# bg_MCU.net
KiCad netlist of a schematic drawn in Altium Designer
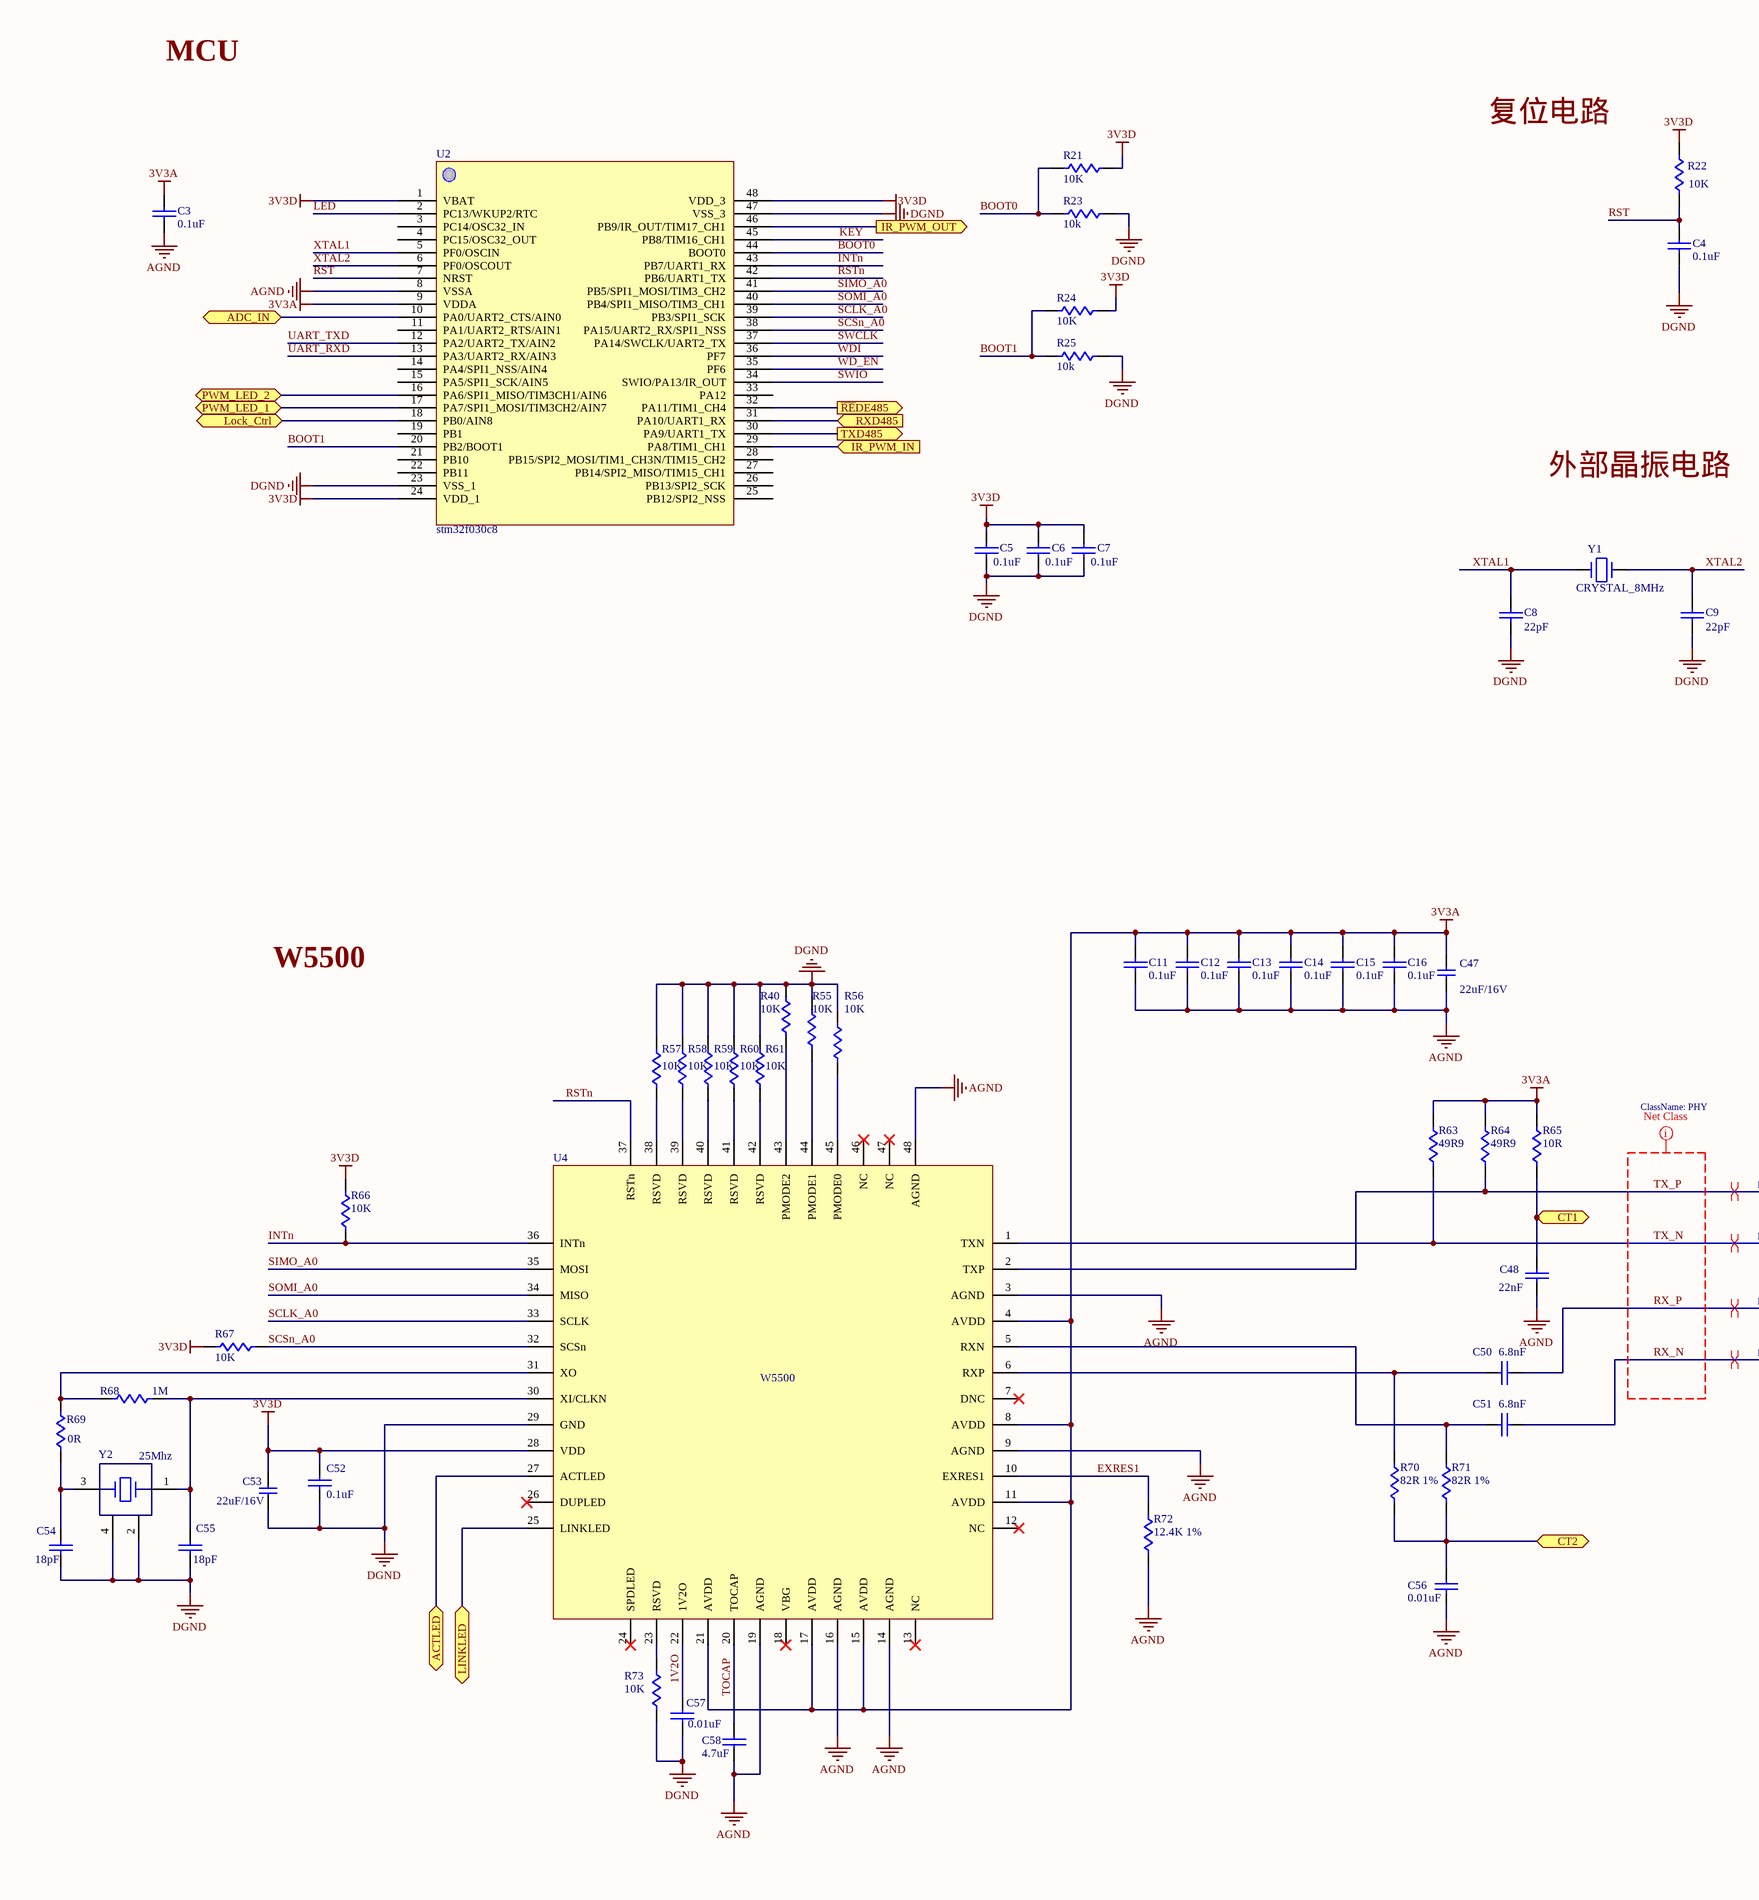
[diagram p0: bg_MCU.SchDoc, left]
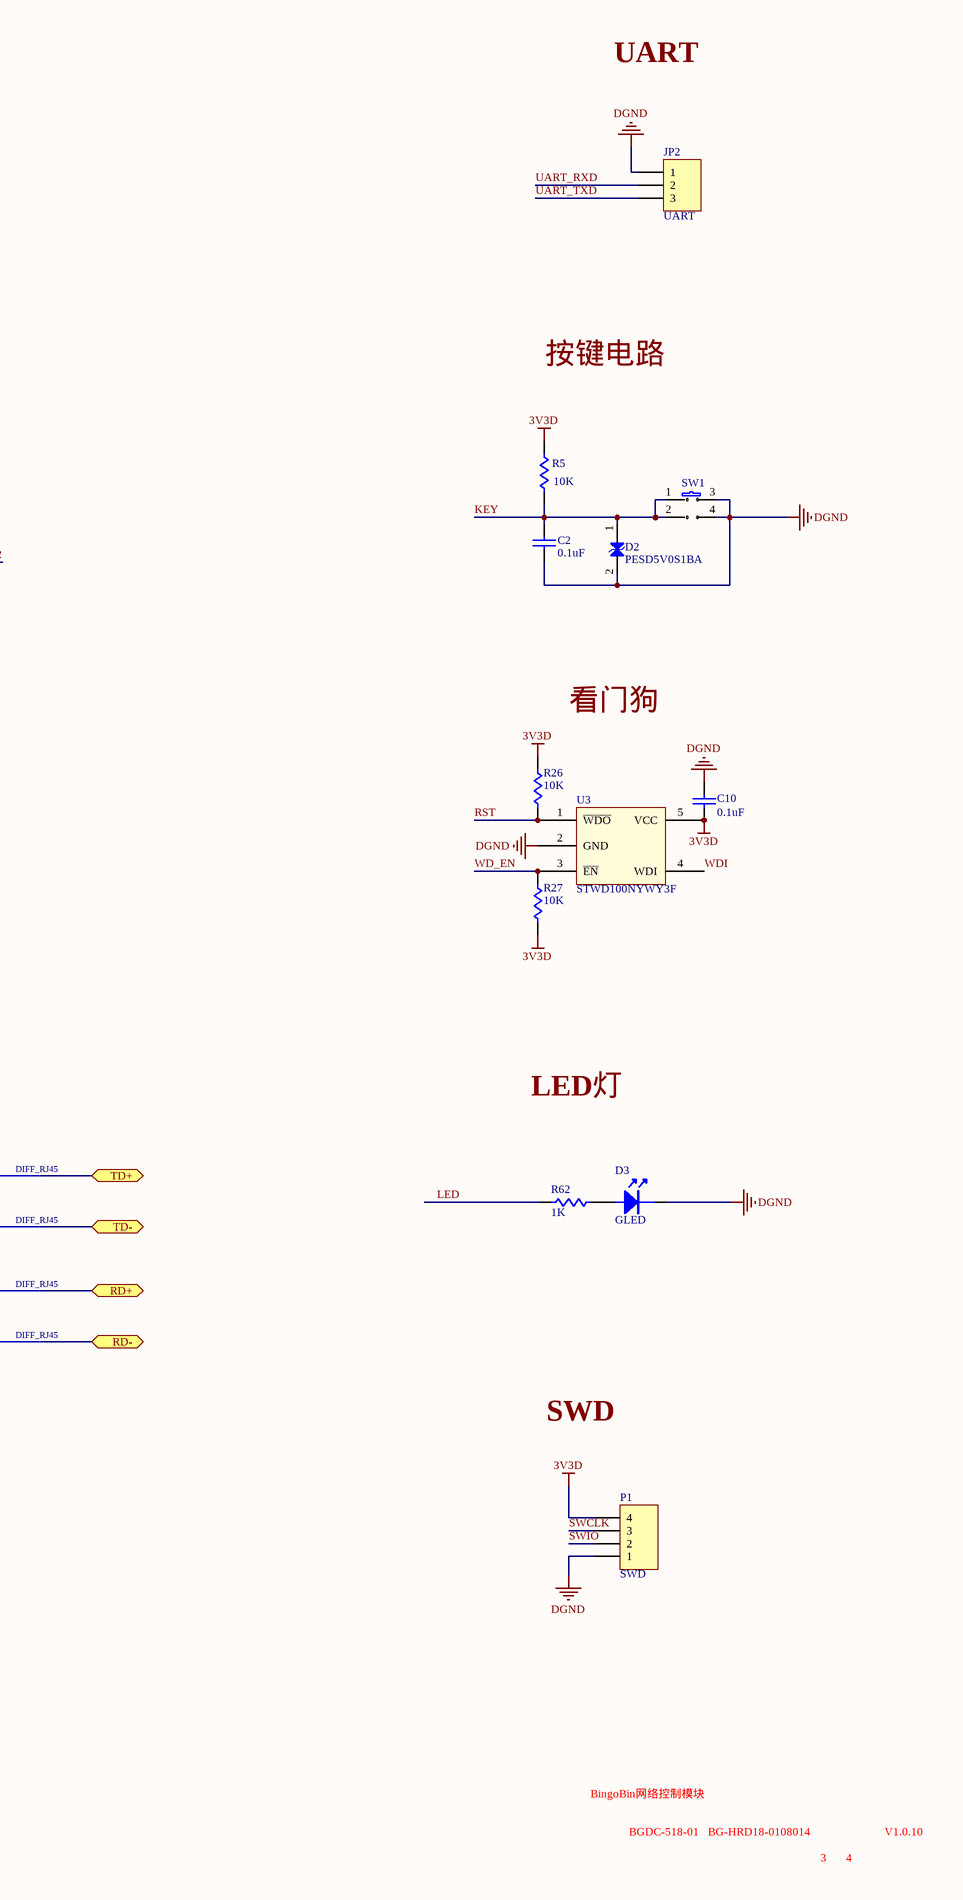
[diagram p1: bg_MCU.SchDoc, right]

(export (version "E")
  (design (tool "Eeschema 10.0.6"))
  (components
    (comp (ref "C2")
      (value "0.1uF")
      (footprint "C0603")
      (description "Capacitor, Ceramic, 0.1uF, 16V, 10%, 0603, X7R")
      (libsource (lib "bg_sch") (part "C0603"))
    )
    (comp (ref "C3")
      (value "0.1uF")
      (footprint "C0603")
      (description "Capacitor, Ceramic, 0.1uF, 16V, 10%, 0603, X7R")
      (libsource (lib "bg_sch") (part "C0603"))
    )
    (comp (ref "C4")
      (value "0.1uF")
      (footprint "C0603")
      (description "Capacitor, Ceramic, 0.1uF, 16V, 10%, 0603, X7R")
      (libsource (lib "bg_sch") (part "C0603"))
    )
    (comp (ref "C5")
      (value "0.1uF")
      (footprint "C0603")
      (description "Capacitor, Ceramic, 0.1uF, 16V, 10%, 0603, X7R")
      (libsource (lib "bg_sch") (part "C0603"))
    )
    (comp (ref "C6")
      (value "0.1uF")
      (footprint "C0603")
      (description "Capacitor, Ceramic, 0.1uF, 16V, 10%, 0603, X7R")
      (libsource (lib "bg_sch") (part "C0603"))
    )
    (comp (ref "C7")
      (value "0.1uF")
      (footprint "C0603")
      (description "Capacitor, Ceramic, 0.1uF, 16V, 10%, 0603, X7R")
      (libsource (lib "bg_sch") (part "C0603"))
    )
    (comp (ref "C8")
      (value "22pF")
      (footprint "C0603")
      (description "Capacitor, Ceramic, 22pF, 50V, 5%, 0603, COG")
      (libsource (lib "bg_sch") (part "C0603"))
    )
    (comp (ref "C9")
      (value "22pF")
      (footprint "C0603")
      (description "Capacitor, Ceramic, 22pF, 50V, 5%, 0603, COG")
      (libsource (lib "bg_sch") (part "C0603"))
    )
    (comp (ref "C10")
      (value "0.1uF")
      (footprint "C0603")
      (description "Capacitor, Ceramic, 0.1uF, 16V, 10%, 0603, X7R")
      (libsource (lib "bg_sch") (part "C0603"))
    )
    (comp (ref "C11")
      (value "0.1uF")
      (footprint "C0603")
      (description "Capacitor, Ceramic, 0.1uF, 16V, 10%, 0603, X7R")
      (libsource (lib "bg_sch") (part "C0603"))
    )
    (comp (ref "C12")
      (value "0.1uF")
      (footprint "C0603")
      (description "Capacitor, Ceramic, 0.1uF, 16V, 10%, 0603, X7R")
      (libsource (lib "bg_sch") (part "C0603"))
    )
    (comp (ref "C13")
      (value "0.1uF")
      (footprint "C0603")
      (description "Capacitor, Ceramic, 0.1uF, 16V, 10%, 0603, X7R")
      (libsource (lib "bg_sch") (part "C0603"))
    )
    (comp (ref "C14")
      (value "0.1uF")
      (footprint "C0603")
      (description "Capacitor, Ceramic, 0.1uF, 16V, 10%, 0603, X7R")
      (libsource (lib "bg_sch") (part "C0603"))
    )
    (comp (ref "C15")
      (value "0.1uF")
      (footprint "C0603")
      (description "Capacitor, Ceramic, 0.1uF, 16V, 10%, 0603, X7R")
      (libsource (lib "bg_sch") (part "C0603"))
    )
    (comp (ref "C16")
      (value "0.1uF")
      (footprint "C0603")
      (description "Capacitor, Ceramic, 0.1uF, 16V, 10%, 0603, X7R")
      (libsource (lib "bg_sch") (part "C0603"))
    )
    (comp (ref "C47")
      (value "22uF/16V")
      (footprint "C1210")
      (description "Capacitor, Ceramic, 10uF,16V, 10%,1210,X5R")
      (fields (field (name "PART NUMBER") "C0603-4µ7") (field (name "PUBLISHER") "Nordic Semiconductor"))
      (libsource (lib "sistalk") (part "CAP_0603"))
    )
    (comp (ref "C48")
      (value "22nF")
      (footprint "C0603")
      (description "Capacitor, Ceramic, 22nF, 25V, 10%, 0603, X7R")
      (libsource (lib "bg_sch") (part "C0603"))
    )
    (comp (ref "C50")
      (value "6.8nF")
      (footprint "C0603")
      (description "Capacitor, Ceramic, 6.8nF, 50V, 10%, 0603, X7R")
      (libsource (lib "bg_sch") (part "C0603"))
    )
    (comp (ref "C51")
      (value "6.8nF")
      (footprint "C0603")
      (description "Capacitor, Ceramic, 6.8nF, 50V, 10%, 0603, X7R")
      (libsource (lib "bg_sch") (part "C0603"))
    )
    (comp (ref "C52")
      (value "0.1uF")
      (footprint "C0603")
      (description "Capacitor, Ceramic, 0.1uF, 16V, 10%, 0603, X7R")
      (libsource (lib "bg_sch") (part "C0603"))
    )
    (comp (ref "C53")
      (value "22uF/16V")
      (footprint "C1210")
      (description "Capacitor, Ceramic, 10uF,16V, 10%,1210,X5R")
      (fields (field (name "PART NUMBER") "C0603-4µ7") (field (name "PUBLISHER") "Nordic Semiconductor"))
      (libsource (lib "sistalk") (part "CAP_0603"))
    )
    (comp (ref "C54")
      (value "18pF")
      (footprint "C0603")
      (description "Capacitor, Ceramic, 18pF, 50V, 5%, 0603, COG")
      (libsource (lib "bg_sch") (part "C0603"))
    )
    (comp (ref "C55")
      (value "18pF")
      (footprint "C0603")
      (description "Capacitor, Ceramic, 18pF, 50V, 5%, 0603, COG")
      (libsource (lib "bg_sch") (part "C0603"))
    )
    (comp (ref "C56")
      (value "0.01uF")
      (footprint "C0603")
      (description "Capacitor, Ceramic, 0.01uF, 50V, 10%, 0603, X7R")
      (libsource (lib "bg_sch") (part "C0603"))
    )
    (comp (ref "C57")
      (value "0.01uF")
      (footprint "C0603")
      (description "Capacitor, Ceramic, 0.01uF, 50V, 10%, 0603, X7R")
      (libsource (lib "bg_sch") (part "C0603"))
    )
    (comp (ref "C58")
      (value "4.7uF")
      (footprint "C0603")
      (description "Capacitor, Ceramic, 4.7uF, 16V, 10%, 0603, X7R")
      (libsource (lib "bg_sch") (part "C0603"))
    )
    (comp (ref "D2")
      (value "PESD5V0S1BA")
      (footprint "SOD323")
      (fields (field (name "MANUFACTURER") "NXP"))
      (libsource (lib "bingo") (part "ESD"))
    )
    (comp (ref "D3")
      (value "GLED")
      (footprint "LED-0805")
      (description "翠绿色 贴片LED ( Iv=220-270mcd @IF=5mA) ")
      (libsource (lib "bg_sch") (part "LED_0805"))
    )
    (comp (ref "JP2")
      (value "UART")
      (footprint "HDR1X3")
      (description "Header, 3-Pin, Single row")
      (fields (field (name "PUBLISHER") "Altium Limited"))
      (libsource (lib "Miscellaneous Connectors") (part "Header 3"))
    )
    (comp (ref "P1")
      (value "SWD")
      (footprint "HDR1X4")
      (description "Header, 4-Pin")
      (fields (field (name "PUBLISHER") "Altium Limited"))
      (libsource (lib "Miscellaneous Connectors") (part "Header 4"))
    )
    (comp (ref "R5")
      (value "10K")
      (footprint "R0603")
      (description "RES, THICK FILM, 4.7K, 5%, 1/10W, 0603")
      (libsource (lib "bg_sch") (part "R0603"))
    )
    (comp (ref "R21")
      (value "10K")
      (footprint "R0603")
      (description "RES, THICK FILM, 4.7K, 5%, 1/10W, 0603")
      (libsource (lib "bg_sch") (part "R0603"))
    )
    (comp (ref "R22")
      (value "10K")
      (footprint "R0603")
      (description "RES, THICK FILM, 4.7K, 5%, 1/10W, 0603")
      (libsource (lib "bg_sch") (part "R0603"))
    )
    (comp (ref "R23")
      (value "10k")
      (footprint "R0603")
      (description "RES, THICK FILM, 4.7K, 5%, 1/10W, 0603")
      (libsource (lib "bg_sch") (part "R0603"))
    )
    (comp (ref "R24")
      (value "10K")
      (footprint "R0603")
      (description "RES, THICK FILM, 4.7K, 5%, 1/10W, 0603")
      (libsource (lib "bg_sch") (part "R0603"))
    )
    (comp (ref "R25")
      (value "10k")
      (footprint "R0603")
      (description "RES, THICK FILM, 4.7K, 5%, 1/10W, 0603")
      (libsource (lib "bg_sch") (part "R0603"))
    )
    (comp (ref "R26")
      (value "10K")
      (footprint "R0603")
      (description "RES, THICK FILM, 10K, 5%, 1/10W, 0603")
      (libsource (lib "bg_sch") (part "R0603"))
    )
    (comp (ref "R27")
      (value "10K")
      (footprint "R0603")
      (description "RES, THICK FILM, 10K, 5%, 1/10W, 0603")
      (libsource (lib "bg_sch") (part "R0603"))
    )
    (comp (ref "R40")
      (value "10K")
      (footprint "R0603")
      (description "RES, THICK FILM, 10K, 5%, 1/10W, 0603")
      (libsource (lib "bg_sch") (part "R0603"))
    )
    (comp (ref "R55")
      (value "10K")
      (footprint "R0603")
      (description "RES, THICK FILM, 10K, 5%, 1/10W, 0603")
      (libsource (lib "bg_sch") (part "R0603"))
    )
    (comp (ref "R56")
      (value "10K")
      (footprint "R0603")
      (description "RES, THICK FILM, 10K, 5%, 1/10W, 0603")
      (libsource (lib "bg_sch") (part "R0603"))
    )
    (comp (ref "R57")
      (value "10K")
      (footprint "R0603")
      (description "RES, THICK FILM, 10K, 5%, 1/10W, 0603")
      (libsource (lib "bg_sch") (part "R0603"))
    )
    (comp (ref "R58")
      (value "10K")
      (footprint "R0603")
      (description "RES, THICK FILM, 10K, 5%, 1/10W, 0603")
      (libsource (lib "bg_sch") (part "R0603"))
    )
    (comp (ref "R59")
      (value "10K")
      (footprint "R0603")
      (description "RES, THICK FILM, 10K, 5%, 1/10W, 0603")
      (libsource (lib "bg_sch") (part "R0603"))
    )
    (comp (ref "R60")
      (value "10K")
      (footprint "R0603")
      (description "RES, THICK FILM, 10K, 5%, 1/10W, 0603")
      (libsource (lib "bg_sch") (part "R0603"))
    )
    (comp (ref "R61")
      (value "10K")
      (footprint "R0603")
      (description "RES, THICK FILM, 10K, 5%, 1/10W, 0603")
      (libsource (lib "bg_sch") (part "R0603"))
    )
    (comp (ref "R62")
      (value "1K")
      (footprint "R0603")
      (description "RES, THICK FILM, 1K, 5%, 1/10W, 0603")
      (libsource (lib "bg_sch") (part "R0603"))
    )
    (comp (ref "R63")
      (value "49R9")
      (footprint "R0603")
      (description "RES, THICK FILM, 49.9 OHM, 1%, 1/10W, 0603")
      (libsource (lib "bg_sch") (part "R0603"))
    )
    (comp (ref "R64")
      (value "49R9")
      (footprint "R0603")
      (description "RES, THICK FILM, 49.9 OHM, 1%, 1/10W, 0603")
      (libsource (lib "bg_sch") (part "R0603"))
    )
    (comp (ref "R65")
      (value "10R")
      (footprint "R0603")
      (description "RES, THICK FILM, 10 OHM, 5%, 1/10W, 0603")
      (libsource (lib "bg_sch") (part "R0603"))
    )
    (comp (ref "R66")
      (value "10K")
      (footprint "R0603")
      (description "RES, THICK FILM, 10K, 5%, 1/10W, 0603")
      (libsource (lib "bg_sch") (part "R0603"))
    )
    (comp (ref "R67")
      (value "10K")
      (footprint "R0603")
      (description "RES, THICK FILM, 10K, 5%, 1/10W, 0603")
      (libsource (lib "bg_sch") (part "R0603"))
    )
    (comp (ref "R68")
      (value "1M")
      (footprint "R0603")
      (description "RES, THICK FILM, 1M, 5%, 1/10W, 0603")
      (libsource (lib "bg_sch") (part "R0603"))
    )
    (comp (ref "R69")
      (value "0R")
      (footprint "R0603")
      (description "RES, THICK FILM, 0 OHM, 1%, 1/10W, 0603")
      (libsource (lib "bg_sch") (part "R0603"))
    )
    (comp (ref "R70")
      (value "82R 1%")
      (footprint "R0603")
      (description "RES, THICK FILM, 82 OHM, 5%, 1/10W, 0603")
      (libsource (lib "bg_sch") (part "R0603"))
    )
    (comp (ref "R71")
      (value "82R 1%")
      (footprint "R0603")
      (description "RES, THICK FILM, 82 OHM, 5%, 1/10W, 0603")
      (libsource (lib "bg_sch") (part "R0603"))
    )
    (comp (ref "R72")
      (value "12.4K 1%")
      (footprint "R0603")
      (description "RES, THICK FILM, 12.4K, 1%, 1/10W, 0603")
      (libsource (lib "bg_sch") (part "R0603"))
    )
    (comp (ref "R73")
      (value "10K")
      (footprint "R0603")
      (description "RES, THICK FILM, 10K, 5%, 1/10W, 0603")
      (libsource (lib "bg_sch") (part "R0603"))
    )
    (comp (ref "SW1")
      (value "K2-6639SP-I4SC-04")
      (footprint "KEY6*6mm")
      (fields (field (name "MANUFACTURER") "韩国韩荣"))
      (libsource (lib "bingo") (part "SW"))
    )
    (comp (ref "U2")
      (value "stm32f030c8")
      (footprint "LQFP48")
      (description "mcu  LQFP-48_7x7x05P")
      (libsource (lib "bingo") (part "stm32f030c8"))
    )
    (comp (ref "U3")
      (value "STWD100NYWY3F")
      (footprint "SOT23-5")
      (description "Watchdog timer circuit/1.6s")
      (libsource (lib "bingo") (part "STWD100"))
    )
    (comp (ref "U4")
      (value "W5500")
      (footprint "W5500-LQFP-48_7x7x05P")
      (description "TCP/IP嵌入式以太网控制器")
      (libsource (lib "bg_sch") (part "W5500"))
    )
    (comp (ref "Y1")
      (value "CRYSTAL_8MHz")
      (footprint "8M_SMD_CRYSTAL")
      (description "20PF 20PPM -40~+85℃ 编带")
      (libsource (lib "bg_sch") (part "CRYSTAL_32.768k"))
    )
    (comp (ref "Y2")
      (value "25Mhz")
      (footprint "25MHz-SMD-3225_4P")
      (description "XTAL S3225 25M 12pF 10ppm 40R -20~70℃ ")
      (libsource (lib "bg_sch") (part "25Mhz"))
    )
  )
  (nets
    (net (code "1") (name "/1V2O") (class "Default")
      (node (ref "C57") (pin "1") (pinfunction "1_1") (pintype "passive"))
      (node (ref "U4") (pin "22") (pinfunction "1V2O_22") (pintype "passive"))
    )
    (net (code "2") (name "/ACTLED") (class "Default")
      (node (ref "U4") (pin "27") (pinfunction "ACTLED_27") (pintype "passive"))
    )
    (net (code "3") (name "/ADC_IN") (class "Default")
      (node (ref "U2") (pin "10") (pinfunction "PA0/UART2_CTS/AIN0_10") (pintype "passive"))
    )
    (net (code "4") (name "/BOOT0") (class "Default")
      (node (ref "R21") (pin "2") (pinfunction "2_2") (pintype "passive"))
      (node (ref "R23") (pin "2") (pinfunction "2_2") (pintype "passive"))
      (node (ref "U2") (pin "44") (pinfunction "BOOT0_44") (pintype "passive"))
    )
    (net (code "5") (name "/BOOT1") (class "Default")
      (node (ref "R24") (pin "2") (pinfunction "2_2") (pintype "passive"))
      (node (ref "R25") (pin "2") (pinfunction "2_2") (pintype "passive"))
      (node (ref "U2") (pin "20") (pinfunction "PB2/BOOT1_20") (pintype "passive"))
    )
    (net (code "6") (name "/CT1") (class "Default")
      (node (ref "C48") (pin "1") (pinfunction "1_1") (pintype "passive"))
      (node (ref "R65") (pin "1") (pinfunction "1_1") (pintype "passive"))
    )
    (net (code "7") (name "/CT2") (class "Default")
      (node (ref "C56") (pin "1") (pinfunction "1_1") (pintype "passive"))
      (node (ref "R70") (pin "1") (pinfunction "1_1") (pintype "passive"))
      (node (ref "R71") (pin "1") (pinfunction "1_1") (pintype "passive"))
    )
    (net (code "8") (name "/EXRES1") (class "Default")
      (node (ref "R72") (pin "2") (pinfunction "2_2") (pintype "passive"))
      (node (ref "U4") (pin "10") (pinfunction "EXRES1_10") (pintype "passive"))
    )
    (net (code "9") (name "/INTn") (class "Default")
      (node (ref "R66") (pin "1") (pinfunction "1_1") (pintype "passive"))
      (node (ref "U2") (pin "43") (pinfunction "PB7/UART1_RX_43") (pintype "passive"))
      (node (ref "U4") (pin "36") (pinfunction "INTn_36") (pintype "passive"))
    )
    (net (code "10") (name "/IR_PWM_IN") (class "Default")
      (node (ref "U2") (pin "29") (pinfunction "PA8/TIM1_CH1_29") (pintype "passive"))
    )
    (net (code "11") (name "/IR_PWM_OUT") (class "Default")
      (node (ref "U2") (pin "46") (pinfunction "PB9/IR_OUT/TIM17_CH1_46") (pintype "passive"))
    )
    (net (code "12") (name "/KEY") (class "Default")
      (node (ref "C2") (pin "2") (pinfunction "2_2") (pintype "passive"))
      (node (ref "D2") (pin "1") (pinfunction "1_1") (pintype "passive"))
      (node (ref "R5") (pin "1") (pinfunction "1_1") (pintype "passive"))
      (node (ref "SW1") (pin "1") (pinfunction "1_1") (pintype "passive"))
      (node (ref "SW1") (pin "2") (pinfunction "2_2") (pintype "passive"))
      (node (ref "U2") (pin "45") (pinfunction "PB8/TIM16_CH1_45") (pintype "passive"))
    )
    (net (code "13") (name "/LED") (class "Default")
      (node (ref "R62") (pin "2") (pinfunction "2_2") (pintype "passive"))
      (node (ref "U2") (pin "2") (pinfunction "PC13/WKUP2/RTC_2") (pintype "passive"))
    )
    (net (code "14") (name "/LINKLED") (class "Default")
      (node (ref "U4") (pin "25") (pinfunction "LINKLED_25") (pintype "passive"))
    )
    (net (code "15") (name "/Lock_Ctrl") (class "Default")
      (node (ref "U2") (pin "18") (pinfunction "PB0/AIN8_18") (pintype "passive"))
    )
    (net (code "16") (name "/PWM_LED_1") (class "Default")
      (node (ref "U2") (pin "17") (pinfunction "PA7/SPI1_MOSI/TIM3CH2/AIN7_17") (pintype "passive"))
    )
    (net (code "17") (name "/PWM_LED_2") (class "Default")
      (node (ref "U2") (pin "16") (pinfunction "PA6/SPI1_MISO/TIM3CH1/AIN6_16") (pintype "passive"))
    )
    (net (code "18") (name "/RST") (class "Default")
      (node (ref "C4") (pin "2") (pinfunction "2_2") (pintype "passive"))
      (node (ref "R22") (pin "1") (pinfunction "1_1") (pintype "passive"))
      (node (ref "R26") (pin "1") (pinfunction "1_1") (pintype "passive"))
      (node (ref "U2") (pin "7") (pinfunction "NRST_7") (pintype "passive"))
      (node (ref "U3") (pin "1") (pinfunction "~{WDO}_1") (pintype "passive"))
    )
    (net (code "19") (name "/RSTn") (class "Default")
      (node (ref "U2") (pin "42") (pinfunction "PB6/UART1_TX_42") (pintype "passive"))
      (node (ref "U4") (pin "37") (pinfunction "RSTn_37") (pintype "passive"))
    )
    (net (code "20") (name "/RXD485") (class "Default")
      (node (ref "U2") (pin "31") (pinfunction "PA10/UART1_RX_31") (pintype "passive"))
    )
    (net (code "21") (name "/RX_N") (class "Default")
      (node (ref "C51") (pin "2") (pinfunction "2_2") (pintype "passive"))
    )
    (net (code "22") (name "/RX_P") (class "Default")
      (node (ref "C50") (pin "2") (pinfunction "2_2") (pintype "passive"))
    )
    (net (code "23") (name "/SCLK_A0") (class "Default")
      (node (ref "U2") (pin "39") (pinfunction "PB3/SPI1_SCK_39") (pintype "passive"))
      (node (ref "U4") (pin "33") (pinfunction "SCLK_33") (pintype "passive"))
    )
    (net (code "24") (name "/SCSn_A0") (class "Default")
      (node (ref "R67") (pin "1") (pinfunction "1_1") (pintype "passive"))
      (node (ref "U2") (pin "38") (pinfunction "PA15/UART2_RX/SPI1_NSS_38") (pintype "passive"))
      (node (ref "U4") (pin "32") (pinfunction "SCSn_32") (pintype "passive"))
    )
    (net (code "25") (name "/SIMO_A0") (class "Default")
      (node (ref "U2") (pin "41") (pinfunction "PB5/SPI1_MOSI/TIM3_CH2_41") (pintype "passive"))
      (node (ref "U4") (pin "35") (pinfunction "MOSI_35") (pintype "passive"))
    )
    (net (code "26") (name "/SOMI_A0") (class "Default")
      (node (ref "U2") (pin "40") (pinfunction "PB4/SPI1_MISO/TIM3_CH1_40") (pintype "passive"))
      (node (ref "U4") (pin "34") (pinfunction "MISO_34") (pintype "passive"))
    )
    (net (code "27") (name "/SWCLK") (class "Default")
      (node (ref "P1") (pin "3") (pinfunction "3_3") (pintype "passive"))
      (node (ref "U2") (pin "37") (pinfunction "PA14/SWCLK/UART2_TX_37") (pintype "passive"))
    )
    (net (code "28") (name "/SWIO") (class "Default")
      (node (ref "P1") (pin "2") (pinfunction "2_2") (pintype "passive"))
      (node (ref "U2") (pin "34") (pinfunction "SWIO/PA13/IR_OUT_34") (pintype "passive"))
    )
    (net (code "29") (name "/TOCAP") (class "Default")
      (node (ref "C58") (pin "1") (pinfunction "1_1") (pintype "passive"))
      (node (ref "U4") (pin "20") (pinfunction "TOCAP_20") (pintype "passive"))
    )
    (net (code "30") (name "/TXD485") (class "Default")
      (node (ref "U2") (pin "30") (pinfunction "PA9/UART1_TX_30") (pintype "passive"))
    )
    (net (code "31") (name "/TX_N") (class "Default")
      (node (ref "R63") (pin "1") (pinfunction "1_1") (pintype "passive"))
      (node (ref "U4") (pin "1") (pinfunction "TXN_1") (pintype "passive"))
    )
    (net (code "32") (name "/TX_P") (class "Default")
      (node (ref "R64") (pin "1") (pinfunction "1_1") (pintype "passive"))
      (node (ref "U4") (pin "2") (pinfunction "TXP_2") (pintype "passive"))
    )
    (net (code "33") (name "/UART_RXD") (class "Default")
      (node (ref "JP2") (pin "2") (pinfunction "2_2") (pintype "passive"))
      (node (ref "U2") (pin "13") (pinfunction "PA3/UART2_RX/AIN3_13") (pintype "passive"))
    )
    (net (code "34") (name "/UART_TXD") (class "Default")
      (node (ref "JP2") (pin "3") (pinfunction "3_3") (pintype "passive"))
      (node (ref "U2") (pin "12") (pinfunction "PA2/UART2_TX/AIN2_12") (pintype "passive"))
    )
    (net (code "35") (name "/WDI") (class "Default")
      (node (ref "U2") (pin "36") (pinfunction "PF7_36") (pintype "passive"))
      (node (ref "U3") (pin "4") (pinfunction "WDI_4") (pintype "passive"))
    )
    (net (code "36") (name "/WD_EN") (class "Default")
      (node (ref "R27") (pin "2") (pinfunction "2_2") (pintype "passive"))
      (node (ref "U2") (pin "35") (pinfunction "PF6_35") (pintype "passive"))
      (node (ref "U3") (pin "3") (pinfunction "~{EN}_3") (pintype "passive"))
    )
    (net (code "37") (name "/XTAL1") (class "Default")
      (node (ref "C8") (pin "1") (pinfunction "1_1") (pintype "passive"))
      (node (ref "U2") (pin "5") (pinfunction "PF0/OSCIN_5") (pintype "passive"))
      (node (ref "Y1") (pin "1") (pinfunction "1_1") (pintype "passive"))
    )
    (net (code "38") (name "/XTAL2") (class "Default")
      (node (ref "C9") (pin "1") (pinfunction "1_1") (pintype "passive"))
      (node (ref "U2") (pin "6") (pinfunction "PF0/OSCOUT_6") (pintype "passive"))
      (node (ref "Y1") (pin "2") (pinfunction "2_2") (pintype "passive"))
    )
    (net (code "39") (name "/~{RE}DE485") (class "Default")
      (node (ref "U2") (pin "32") (pinfunction "PA11/TIM1_CH4_32") (pintype "passive"))
    )
    (net (code "40") (name "3V3A") (class "Default")
      (node (ref "C11") (pin "1") (pinfunction "1_1") (pintype "passive"))
      (node (ref "C12") (pin "1") (pinfunction "1_1") (pintype "passive"))
      (node (ref "C13") (pin "1") (pinfunction "1_1") (pintype "passive"))
      (node (ref "C14") (pin "1") (pinfunction "1_1") (pintype "passive"))
      (node (ref "C15") (pin "1") (pinfunction "1_1") (pintype "passive"))
      (node (ref "C16") (pin "1") (pinfunction "1_1") (pintype "passive"))
      (node (ref "C3") (pin "1") (pinfunction "1_1") (pintype "passive"))
      (node (ref "C47") (pin "2") (pinfunction "2_2") (pintype "passive"))
      (node (ref "R63") (pin "2") (pinfunction "2_2") (pintype "passive"))
      (node (ref "R64") (pin "2") (pinfunction "2_2") (pintype "passive"))
      (node (ref "R65") (pin "2") (pinfunction "2_2") (pintype "passive"))
      (node (ref "U2") (pin "9") (pinfunction "VDDA_9") (pintype "passive"))
      (node (ref "U4") (pin "11") (pinfunction "AVDD_11") (pintype "passive"))
      (node (ref "U4") (pin "15") (pinfunction "AVDD_15") (pintype "passive"))
      (node (ref "U4") (pin "17") (pinfunction "AVDD_17") (pintype "passive"))
      (node (ref "U4") (pin "21") (pinfunction "AVDD_21") (pintype "passive"))
      (node (ref "U4") (pin "4") (pinfunction "AVDD_4") (pintype "passive"))
      (node (ref "U4") (pin "8") (pinfunction "AVDD_8") (pintype "passive"))
    )
    (net (code "41") (name "3V3D") (class "Default")
      (node (ref "C10") (pin "2") (pinfunction "2_2") (pintype "passive"))
      (node (ref "C5") (pin "2") (pinfunction "2_2") (pintype "passive"))
      (node (ref "C52") (pin "1") (pinfunction "1_1") (pintype "passive"))
      (node (ref "C53") (pin "2") (pinfunction "2_2") (pintype "passive"))
      (node (ref "C6") (pin "2") (pinfunction "2_2") (pintype "passive"))
      (node (ref "C7") (pin "2") (pinfunction "2_2") (pintype "passive"))
      (node (ref "P1") (pin "4") (pinfunction "4_4") (pintype "passive"))
      (node (ref "R21") (pin "1") (pinfunction "1_1") (pintype "passive"))
      (node (ref "R22") (pin "2") (pinfunction "2_2") (pintype "passive"))
      (node (ref "R24") (pin "1") (pinfunction "1_1") (pintype "passive"))
      (node (ref "R26") (pin "2") (pinfunction "2_2") (pintype "passive"))
      (node (ref "R27") (pin "1") (pinfunction "1_1") (pintype "passive"))
      (node (ref "R5") (pin "2") (pinfunction "2_2") (pintype "passive"))
      (node (ref "R66") (pin "2") (pinfunction "2_2") (pintype "passive"))
      (node (ref "R67") (pin "2") (pinfunction "2_2") (pintype "passive"))
      (node (ref "U2") (pin "1") (pinfunction "VBAT_1") (pintype "passive"))
      (node (ref "U2") (pin "24") (pinfunction "VDD_1_24") (pintype "passive"))
      (node (ref "U2") (pin "48") (pinfunction "VDD_3_48") (pintype "passive"))
      (node (ref "U3") (pin "5") (pinfunction "VCC_5") (pintype "passive"))
      (node (ref "U4") (pin "28") (pinfunction "VDD_28") (pintype "passive"))
    )
    (net (code "42") (name "AGND") (class "Default")
      (node (ref "C11") (pin "2") (pinfunction "2_2") (pintype "passive"))
      (node (ref "C12") (pin "2") (pinfunction "2_2") (pintype "passive"))
      (node (ref "C13") (pin "2") (pinfunction "2_2") (pintype "passive"))
      (node (ref "C14") (pin "2") (pinfunction "2_2") (pintype "passive"))
      (node (ref "C15") (pin "2") (pinfunction "2_2") (pintype "passive"))
      (node (ref "C16") (pin "2") (pinfunction "2_2") (pintype "passive"))
      (node (ref "C3") (pin "2") (pinfunction "2_2") (pintype "passive"))
      (node (ref "C47") (pin "1") (pinfunction "1_1") (pintype "passive"))
      (node (ref "C48") (pin "2") (pinfunction "2_2") (pintype "passive"))
      (node (ref "C56") (pin "2") (pinfunction "2_2") (pintype "passive"))
      (node (ref "C58") (pin "2") (pinfunction "2_2") (pintype "passive"))
      (node (ref "R72") (pin "1") (pinfunction "1_1") (pintype "passive"))
      (node (ref "U2") (pin "8") (pinfunction "VSSA_8") (pintype "passive"))
      (node (ref "U4") (pin "14") (pinfunction "AGND_14") (pintype "passive"))
      (node (ref "U4") (pin "16") (pinfunction "AGND_16") (pintype "passive"))
      (node (ref "U4") (pin "19") (pinfunction "AGND_19") (pintype "passive"))
      (node (ref "U4") (pin "3") (pinfunction "AGND_3") (pintype "passive"))
      (node (ref "U4") (pin "48") (pinfunction "AGND_48") (pintype "passive"))
      (node (ref "U4") (pin "9") (pinfunction "AGND_9") (pintype "passive"))
    )
    (net (code "43") (name "DGND") (class "Default")
      (node (ref "C10") (pin "1") (pinfunction "1_1") (pintype "passive"))
      (node (ref "C2") (pin "1") (pinfunction "1_1") (pintype "passive"))
      (node (ref "C4") (pin "1") (pinfunction "1_1") (pintype "passive"))
      (node (ref "C5") (pin "1") (pinfunction "1_1") (pintype "passive"))
      (node (ref "C52") (pin "2") (pinfunction "2_2") (pintype "passive"))
      (node (ref "C53") (pin "1") (pinfunction "1_1") (pintype "passive"))
      (node (ref "C54") (pin "2") (pinfunction "2_2") (pintype "passive"))
      (node (ref "C55") (pin "2") (pinfunction "2_2") (pintype "passive"))
      (node (ref "C57") (pin "2") (pinfunction "2_2") (pintype "passive"))
      (node (ref "C6") (pin "1") (pinfunction "1_1") (pintype "passive"))
      (node (ref "C7") (pin "1") (pinfunction "1_1") (pintype "passive"))
      (node (ref "C8") (pin "2") (pinfunction "2_2") (pintype "passive"))
      (node (ref "C9") (pin "2") (pinfunction "2_2") (pintype "passive"))
      (node (ref "D2") (pin "2") (pinfunction "2_2") (pintype "passive"))
      (node (ref "D3") (pin "2") (pinfunction "2_2") (pintype "passive"))
      (node (ref "JP2") (pin "1") (pinfunction "1_1") (pintype "passive"))
      (node (ref "P1") (pin "1") (pinfunction "1_1") (pintype "passive"))
      (node (ref "R23") (pin "1") (pinfunction "1_1") (pintype "passive"))
      (node (ref "R25") (pin "1") (pinfunction "1_1") (pintype "passive"))
      (node (ref "R40") (pin "2") (pinfunction "2_2") (pintype "passive"))
      (node (ref "R55") (pin "2") (pinfunction "2_2") (pintype "passive"))
      (node (ref "R56") (pin "2") (pinfunction "2_2") (pintype "passive"))
      (node (ref "R57") (pin "2") (pinfunction "2_2") (pintype "passive"))
      (node (ref "R58") (pin "2") (pinfunction "2_2") (pintype "passive"))
      (node (ref "R59") (pin "2") (pinfunction "2_2") (pintype "passive"))
      (node (ref "R60") (pin "2") (pinfunction "2_2") (pintype "passive"))
      (node (ref "R61") (pin "2") (pinfunction "2_2") (pintype "passive"))
      (node (ref "R73") (pin "1") (pinfunction "1_1") (pintype "passive"))
      (node (ref "SW1") (pin "3") (pinfunction "3_3") (pintype "passive"))
      (node (ref "SW1") (pin "4") (pinfunction "4_4") (pintype "passive"))
      (node (ref "U2") (pin "23") (pinfunction "VSS_1_23") (pintype "passive"))
      (node (ref "U2") (pin "47") (pinfunction "VSS_3_47") (pintype "passive"))
      (node (ref "U3") (pin "2") (pinfunction "GND_2") (pintype "passive"))
      (node (ref "U4") (pin "29") (pinfunction "GND_29") (pintype "passive"))
      (node (ref "Y2") (pin "2") (pinfunction "2_2") (pintype "passive"))
      (node (ref "Y2") (pin "4") (pinfunction "3_4") (pintype "passive"))
    )
    (net (code "44") (name "Net-(D3-Pad1)") (class "Default")
      (node (ref "D3") (pin "1") (pinfunction "1_1") (pintype "passive"))
      (node (ref "R62") (pin "1") (pinfunction "1_1") (pintype "passive"))
    )
    (net (code "45") (name "Net-(R57-Pad1)") (class "Default")
      (node (ref "R57") (pin "1") (pinfunction "1_1") (pintype "passive"))
      (node (ref "U4") (pin "38") (pinfunction "RSVD_38") (pintype "passive"))
    )
    (net (code "46") (name "Net-(R58-Pad1)") (class "Default")
      (node (ref "R58") (pin "1") (pinfunction "1_1") (pintype "passive"))
      (node (ref "U4") (pin "39") (pinfunction "RSVD_39") (pintype "passive"))
    )
    (net (code "47") (name "Net-(R59-Pad1)") (class "Default")
      (node (ref "R59") (pin "1") (pinfunction "1_1") (pintype "passive"))
      (node (ref "U4") (pin "40") (pinfunction "RSVD_40") (pintype "passive"))
    )
    (net (code "48") (name "Net-(R60-Pad1)") (class "Default")
      (node (ref "R60") (pin "1") (pinfunction "1_1") (pintype "passive"))
      (node (ref "U4") (pin "41") (pinfunction "RSVD_41") (pintype "passive"))
    )
    (net (code "49") (name "Net-(R61-Pad1)") (class "Default")
      (node (ref "R61") (pin "1") (pinfunction "1_1") (pintype "passive"))
      (node (ref "U4") (pin "42") (pinfunction "RSVD_42") (pintype "passive"))
    )
    (net (code "50") (name "Net-(R73-Pad2)") (class "Default")
      (node (ref "R73") (pin "2") (pinfunction "2_2") (pintype "passive"))
      (node (ref "U4") (pin "23") (pinfunction "RSVD_23") (pintype "passive"))
    )
    (net (code "51") (name "Net-(U4-PMODE0)") (class "Default")
      (node (ref "R56") (pin "1") (pinfunction "1_1") (pintype "passive"))
      (node (ref "U4") (pin "45") (pinfunction "PMODE0_45") (pintype "passive"))
    )
    (net (code "52") (name "Net-(U4-PMODE1)") (class "Default")
      (node (ref "R55") (pin "1") (pinfunction "1_1") (pintype "passive"))
      (node (ref "U4") (pin "44") (pinfunction "PMODE1_44") (pintype "passive"))
    )
    (net (code "53") (name "Net-(U4-PMODE2)") (class "Default")
      (node (ref "R40") (pin "1") (pinfunction "1_1") (pintype "passive"))
      (node (ref "U4") (pin "43") (pinfunction "PMODE2_43") (pintype "passive"))
    )
    (net (code "54") (name "Net-(U4-RXN)") (class "Default")
      (node (ref "C51") (pin "1") (pinfunction "1_1") (pintype "passive"))
      (node (ref "R71") (pin "2") (pinfunction "2_2") (pintype "passive"))
      (node (ref "U4") (pin "5") (pinfunction "RXN_5") (pintype "passive"))
    )
    (net (code "55") (name "Net-(U4-RXP)") (class "Default")
      (node (ref "C50") (pin "1") (pinfunction "1_1") (pintype "passive"))
      (node (ref "R70") (pin "2") (pinfunction "2_2") (pintype "passive"))
      (node (ref "U4") (pin "6") (pinfunction "RXP_6") (pintype "passive"))
    )
    (net (code "56") (name "Net-(U4-XI{slash}CLKN)") (class "Default")
      (node (ref "C55") (pin "1") (pinfunction "1_1") (pintype "passive"))
      (node (ref "R68") (pin "1") (pinfunction "1_1") (pintype "passive"))
      (node (ref "U4") (pin "30") (pinfunction "XI/CLKN_30") (pintype "passive"))
      (node (ref "Y2") (pin "1") (pinfunction "1_1") (pintype "passive"))
    )
    (net (code "57") (name "Net-(U4-XO)") (class "Default")
      (node (ref "R68") (pin "2") (pinfunction "2_2") (pintype "passive"))
      (node (ref "R69") (pin "2") (pinfunction "2_2") (pintype "passive"))
      (node (ref "U4") (pin "31") (pinfunction "XO_31") (pintype "passive"))
    )
    (net (code "58") (name "Net-(Y2-4)") (class "Default")
      (node (ref "C54") (pin "1") (pinfunction "1_1") (pintype "passive"))
      (node (ref "R69") (pin "1") (pinfunction "1_1") (pintype "passive"))
      (node (ref "Y2") (pin "3") (pinfunction "4_3") (pintype "passive"))
    )
    (net (code "59") (name "unconnected-(U2-PA1{slash}UART2_RTS{slash}AIN1-Pad11)") (class "Default")
      (node (ref "U2") (pin "11") (pinfunction "PA1/UART2_RTS/AIN1_11") (pintype "passive"))
    )
    (net (code "60") (name "unconnected-(U2-PA4{slash}SPI1_NSS{slash}AIN4-Pad14)") (class "Default")
      (node (ref "U2") (pin "14") (pinfunction "PA4/SPI1_NSS/AIN4_14") (pintype "passive"))
    )
    (net (code "61") (name "unconnected-(U2-PA5{slash}SPI1_SCK{slash}AIN5-Pad15)") (class "Default")
      (node (ref "U2") (pin "15") (pinfunction "PA5/SPI1_SCK/AIN5_15") (pintype "passive"))
    )
    (net (code "62") (name "unconnected-(U2-PA12-Pad33)") (class "Default")
      (node (ref "U2") (pin "33") (pinfunction "PA12_33") (pintype "passive"))
    )
    (net (code "63") (name "unconnected-(U2-PB1-Pad19)") (class "Default")
      (node (ref "U2") (pin "19") (pinfunction "PB1_19") (pintype "passive"))
    )
    (net (code "64") (name "unconnected-(U2-PB10-Pad21)") (class "Default")
      (node (ref "U2") (pin "21") (pinfunction "PB10_21") (pintype "passive"))
    )
    (net (code "65") (name "unconnected-(U2-PB11-Pad22)") (class "Default")
      (node (ref "U2") (pin "22") (pinfunction "PB11_22") (pintype "passive"))
    )
    (net (code "66") (name "unconnected-(U2-PB12{slash}SPI2_NSS-Pad25)") (class "Default")
      (node (ref "U2") (pin "25") (pinfunction "PB12/SPI2_NSS_25") (pintype "passive"))
    )
    (net (code "67") (name "unconnected-(U2-PB13{slash}SPI2_SCK-Pad26)") (class "Default")
      (node (ref "U2") (pin "26") (pinfunction "PB13/SPI2_SCK_26") (pintype "passive"))
    )
    (net (code "68") (name "unconnected-(U2-PB14{slash}SPI2_MISO{slash}TIM15_CH1-Pad27)") (class "Default")
      (node (ref "U2") (pin "27") (pinfunction "PB14/SPI2_MISO/TIM15_CH1_27") (pintype "passive"))
    )
    (net (code "69") (name "unconnected-(U2-PB15{slash}SPI2_MOSI{slash}TIM1_CH3N{slash}TIM15_CH2-Pad28)") (class "Default")
      (node (ref "U2") (pin "28") (pinfunction "PB15/SPI2_MOSI/TIM1_CH3N/TIM15_CH2_28") (pintype "passive"))
    )
    (net (code "70") (name "unconnected-(U2-PC14{slash}OSC32_IN-Pad3)") (class "Default")
      (node (ref "U2") (pin "3") (pinfunction "PC14/OSC32_IN_3") (pintype "passive"))
    )
    (net (code "71") (name "unconnected-(U2-PC15{slash}OSC32_OUT-Pad4)") (class "Default")
      (node (ref "U2") (pin "4") (pinfunction "PC15/OSC32_OUT_4") (pintype "passive"))
    )
    (net (code "72") (name "unconnected-(U4-DNC-Pad7)") (class "Default")
      (node (ref "U4") (pin "7") (pinfunction "DNC_7") (pintype "passive+no_connect"))
    )
    (net (code "73") (name "unconnected-(U4-DUPLED-Pad26)") (class "Default")
      (node (ref "U4") (pin "26") (pinfunction "DUPLED_26") (pintype "passive+no_connect"))
    )
    (net (code "74") (name "unconnected-(U4-NC-Pad12)") (class "Default")
      (node (ref "U4") (pin "12") (pinfunction "NC_12") (pintype "passive+no_connect"))
    )
    (net (code "75") (name "unconnected-(U4-NC-Pad13)") (class "Default")
      (node (ref "U4") (pin "13") (pinfunction "NC_13") (pintype "passive+no_connect"))
    )
    (net (code "76") (name "unconnected-(U4-NC-Pad46)") (class "Default")
      (node (ref "U4") (pin "46") (pinfunction "NC_46") (pintype "passive+no_connect"))
    )
    (net (code "77") (name "unconnected-(U4-NC-Pad47)") (class "Default")
      (node (ref "U4") (pin "47") (pinfunction "NC_47") (pintype "passive+no_connect"))
    )
    (net (code "78") (name "unconnected-(U4-SPDLED-Pad24)") (class "Default")
      (node (ref "U4") (pin "24") (pinfunction "SPDLED_24") (pintype "passive+no_connect"))
    )
    (net (code "79") (name "unconnected-(U4-VBG-Pad18)") (class "Default")
      (node (ref "U4") (pin "18") (pinfunction "VBG_18") (pintype "passive+no_connect"))
    )
  )
)
